# beverage-flow-meters-board.net
KiCad netlist of a schematic drawn in EAGLE
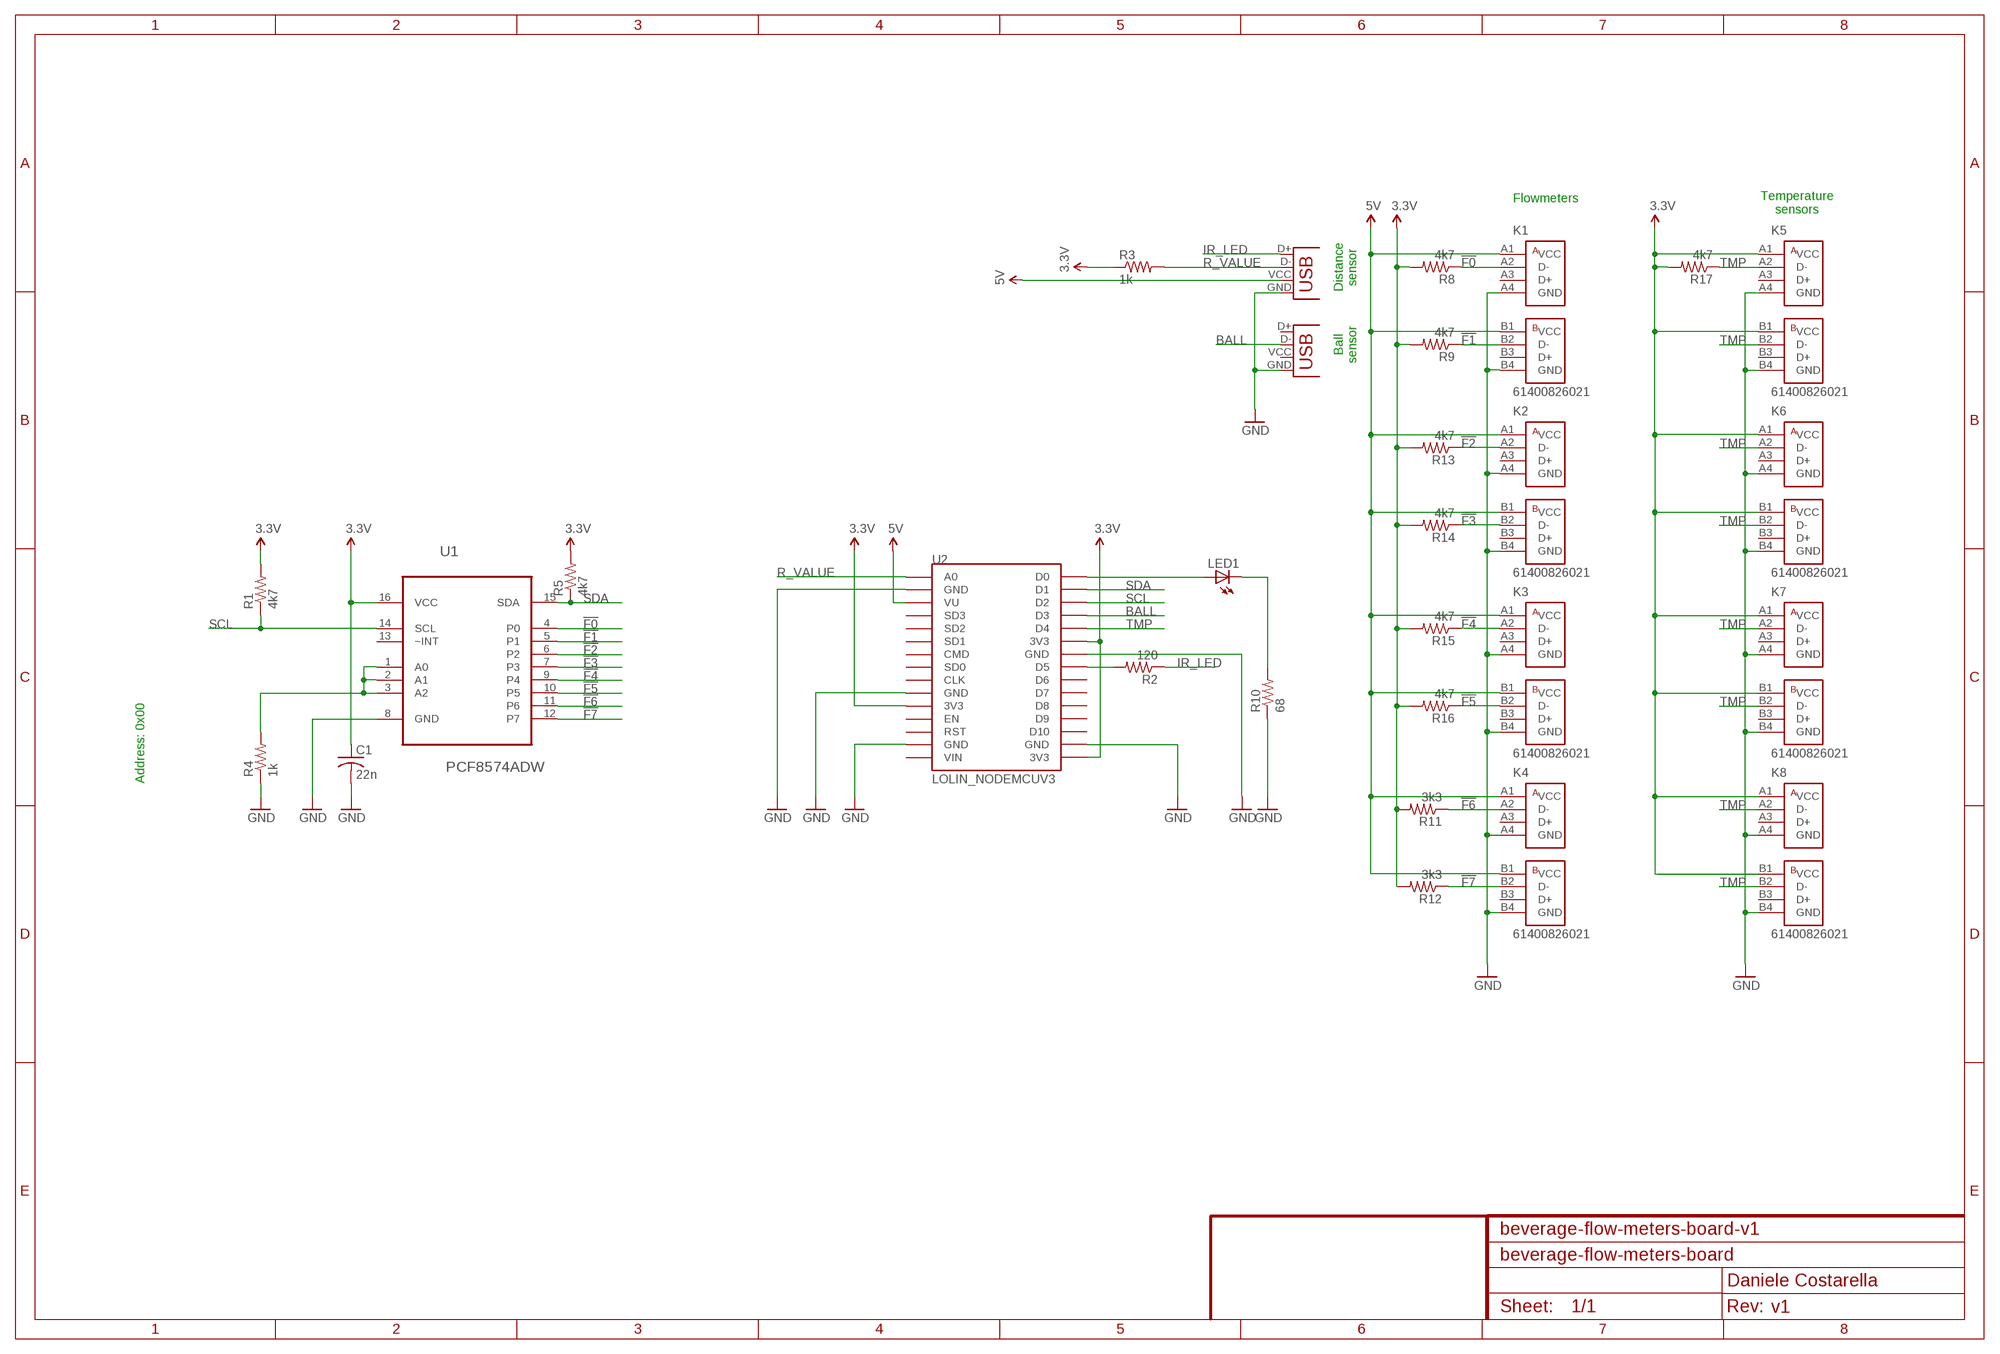
[diagram p0: schematic, sheet 1]

(export (version "E")
  (design (tool "Eeschema 10.0.6"))
  (components
    (comp (ref "C1")
      (value "22n")
      (footprint "eagle-import:C1206")
      (libsource (lib "eagle-import") (part "C-USC1206"))
    )
    (comp (ref "JP1")
      (value "USB-A-H")
      (footprint "eagle-import:USB-A-VERT")
      (libsource (lib "eagle-import") (part "USB-A-H"))
    )
    (comp (ref "JP2")
      (value "USB-A-H")
      (footprint "eagle-import:USB-A-VERT")
      (libsource (lib "eagle-import") (part "USB-A-H"))
    )
    (comp (ref "K1")
      (value "61400826021")
      (footprint "eagle-import:61400826021")
      (libsource (lib "eagle-import") (part "61400826021"))
    )
    (comp (ref "K2")
      (value "61400826021")
      (footprint "eagle-import:61400826021")
      (libsource (lib "eagle-import") (part "61400826021"))
    )
    (comp (ref "K3")
      (value "61400826021")
      (footprint "eagle-import:61400826021")
      (libsource (lib "eagle-import") (part "61400826021"))
    )
    (comp (ref "K4")
      (value "61400826021")
      (footprint "eagle-import:61400826021")
      (libsource (lib "eagle-import") (part "61400826021"))
    )
    (comp (ref "K5")
      (value "61400826021")
      (footprint "eagle-import:61400826021")
      (libsource (lib "eagle-import") (part "61400826021"))
    )
    (comp (ref "K6")
      (value "61400826021")
      (footprint "eagle-import:61400826021")
      (libsource (lib "eagle-import") (part "61400826021"))
    )
    (comp (ref "K7")
      (value "61400826021")
      (footprint "eagle-import:61400826021")
      (libsource (lib "eagle-import") (part "61400826021"))
    )
    (comp (ref "K8")
      (value "61400826021")
      (footprint "eagle-import:61400826021")
      (libsource (lib "eagle-import") (part "61400826021"))
    )
    (comp (ref "LED1")
      (value "LEDCHIP-LED0603")
      (footprint "eagle-import:CHIP-LED0603")
      (libsource (lib "eagle-import") (part "LEDCHIP-LED0603"))
    )
    (comp (ref "R1")
      (value "4k7")
      (footprint "eagle-import:R0603")
      (libsource (lib "eagle-import") (part "R-US_R0603"))
    )
    (comp (ref "R2")
      (value "120")
      (footprint "eagle-import:R0603")
      (libsource (lib "eagle-import") (part "R-US_R0603"))
    )
    (comp (ref "R3")
      (value "1k")
      (footprint "eagle-import:R0603")
      (libsource (lib "eagle-import") (part "R-US_R0603"))
    )
    (comp (ref "R4")
      (value "1k")
      (footprint "eagle-import:R0603")
      (libsource (lib "eagle-import") (part "R-US_R0603"))
    )
    (comp (ref "R5")
      (value "4k7")
      (footprint "eagle-import:R0603")
      (libsource (lib "eagle-import") (part "R-US_R0603"))
    )
    (comp (ref "R8")
      (value "4k7")
      (footprint "eagle-import:R0603")
      (libsource (lib "eagle-import") (part "R-US_R0603"))
    )
    (comp (ref "R9")
      (value "4k7")
      (footprint "eagle-import:R0603")
      (libsource (lib "eagle-import") (part "R-US_R0603"))
    )
    (comp (ref "R10")
      (value "68")
      (footprint "eagle-import:R0603")
      (libsource (lib "eagle-import") (part "R-US_R0603"))
    )
    (comp (ref "R11")
      (value "3k3")
      (footprint "eagle-import:R0603")
      (libsource (lib "eagle-import") (part "R-US_R0603"))
    )
    (comp (ref "R12")
      (value "3k3")
      (footprint "eagle-import:R0603")
      (libsource (lib "eagle-import") (part "R-US_R0603"))
    )
    (comp (ref "R13")
      (value "4k7")
      (footprint "eagle-import:R0603")
      (libsource (lib "eagle-import") (part "R-US_R0603"))
    )
    (comp (ref "R14")
      (value "4k7")
      (footprint "eagle-import:R0603")
      (libsource (lib "eagle-import") (part "R-US_R0603"))
    )
    (comp (ref "R15")
      (value "4k7")
      (footprint "eagle-import:R0603")
      (libsource (lib "eagle-import") (part "R-US_R0603"))
    )
    (comp (ref "R16")
      (value "4k7")
      (footprint "eagle-import:R0603")
      (libsource (lib "eagle-import") (part "R-US_R0603"))
    )
    (comp (ref "R17")
      (value "4k7")
      (footprint "eagle-import:R0603")
      (libsource (lib "eagle-import") (part "R-US_R0603"))
    )
    (comp (ref "U1")
      (value "PCF8574ADW")
      (footprint "eagle-import:SOIC127P1030X265-16N")
      (libsource (lib "eagle-import") (part "PCF8574ADW"))
    )
    (comp (ref "U2")
      (value "LOLIN_NODEMCUV3")
      (footprint "eagle-import:ESP12E_DEVKIT_CHINA")
      (libsource (lib "eagle-import") (part "LOLIN_NODEMCUV3"))
    )
  )
  (nets
    (net (code "1") (name "/BALL") (class "Default")
      (node (ref "JP2") (pin "D-") (pinfunction "D-_D-") (pintype "bidirectional"))
      (node (ref "U2") (pin "D3") (pinfunction "D3_D3") (pintype "bidirectional"))
    )
    (net (code "2") (name "/IR_LED") (class "Default")
      (node (ref "JP1") (pin "D+") (pinfunction "D+_D+") (pintype "bidirectional"))
      (node (ref "R2") (pin "1") (pinfunction "1_1") (pintype "passive"))
    )
    (net (code "3") (name "/R_VALUE") (class "Default")
      (node (ref "JP1") (pin "D-") (pinfunction "D-_D-") (pintype "bidirectional"))
      (node (ref "R3") (pin "2") (pinfunction "2_2") (pintype "passive"))
      (node (ref "U2") (pin "A0") (pinfunction "A0_A0") (pintype "bidirectional"))
    )
    (net (code "4") (name "/SCL") (class "Default")
      (node (ref "R1") (pin "1") (pinfunction "1_1") (pintype "passive"))
      (node (ref "U1") (pin "14") (pinfunction "SCL_14") (pintype "input"))
      (node (ref "U2") (pin "D2") (pinfunction "D2_D2") (pintype "bidirectional"))
    )
    (net (code "5") (name "/SDA") (class "Default")
      (node (ref "R5") (pin "1") (pinfunction "1_1") (pintype "passive"))
      (node (ref "U1") (pin "15") (pinfunction "SDA_15") (pintype "bidirectional"))
      (node (ref "U2") (pin "D1") (pinfunction "D1_D1") (pintype "bidirectional"))
    )
    (net (code "6") (name "/TMP") (class "Default")
      (node (ref "K5") (pin "A2") (pinfunction "D-_A2") (pintype "bidirectional"))
      (node (ref "K5") (pin "B2") (pinfunction "D-_B2") (pintype "bidirectional"))
      (node (ref "K6") (pin "A2") (pinfunction "D-_A2") (pintype "bidirectional"))
      (node (ref "K6") (pin "B2") (pinfunction "D-_B2") (pintype "bidirectional"))
      (node (ref "K7") (pin "A2") (pinfunction "D-_A2") (pintype "bidirectional"))
      (node (ref "K7") (pin "B2") (pinfunction "D-_B2") (pintype "bidirectional"))
      (node (ref "K8") (pin "A2") (pinfunction "D-_A2") (pintype "bidirectional"))
      (node (ref "K8") (pin "B2") (pinfunction "D-_B2") (pintype "bidirectional"))
      (node (ref "R17") (pin "1") (pinfunction "1_1") (pintype "passive"))
      (node (ref "U2") (pin "D4") (pinfunction "D4_D4") (pintype "bidirectional"))
    )
    (net (code "7") (name "/~{F0}") (class "Default")
      (node (ref "K1") (pin "A2") (pinfunction "D-_A2") (pintype "bidirectional"))
      (node (ref "R8") (pin "1") (pinfunction "1_1") (pintype "passive"))
      (node (ref "U1") (pin "4") (pinfunction "P0_4") (pintype "bidirectional"))
    )
    (net (code "8") (name "/~{F1}") (class "Default")
      (node (ref "K1") (pin "B2") (pinfunction "D-_B2") (pintype "bidirectional"))
      (node (ref "R9") (pin "1") (pinfunction "1_1") (pintype "passive"))
      (node (ref "U1") (pin "5") (pinfunction "P1_5") (pintype "bidirectional"))
    )
    (net (code "9") (name "/~{F2}") (class "Default")
      (node (ref "K2") (pin "A2") (pinfunction "D-_A2") (pintype "bidirectional"))
      (node (ref "R13") (pin "1") (pinfunction "1_1") (pintype "passive"))
      (node (ref "U1") (pin "6") (pinfunction "P2_6") (pintype "bidirectional"))
    )
    (net (code "10") (name "/~{F3}") (class "Default")
      (node (ref "K2") (pin "B2") (pinfunction "D-_B2") (pintype "bidirectional"))
      (node (ref "R14") (pin "1") (pinfunction "1_1") (pintype "passive"))
      (node (ref "U1") (pin "7") (pinfunction "P3_7") (pintype "bidirectional"))
    )
    (net (code "11") (name "/~{F4}") (class "Default")
      (node (ref "K3") (pin "A2") (pinfunction "D-_A2") (pintype "bidirectional"))
      (node (ref "R15") (pin "1") (pinfunction "1_1") (pintype "passive"))
      (node (ref "U1") (pin "9") (pinfunction "P4_9") (pintype "bidirectional"))
    )
    (net (code "12") (name "/~{F5}") (class "Default")
      (node (ref "K3") (pin "B2") (pinfunction "D-_B2") (pintype "bidirectional"))
      (node (ref "R16") (pin "1") (pinfunction "1_1") (pintype "passive"))
      (node (ref "U1") (pin "10") (pinfunction "P5_10") (pintype "bidirectional"))
    )
    (net (code "13") (name "/~{F6}") (class "Default")
      (node (ref "K4") (pin "A2") (pinfunction "D-_A2") (pintype "bidirectional"))
      (node (ref "R11") (pin "1") (pinfunction "1_1") (pintype "passive"))
      (node (ref "U1") (pin "11") (pinfunction "P6_11") (pintype "bidirectional"))
    )
    (net (code "14") (name "/~{F7}") (class "Default")
      (node (ref "K4") (pin "B2") (pinfunction "D-_B2") (pintype "bidirectional"))
      (node (ref "R12") (pin "1") (pinfunction "1_1") (pintype "passive"))
      (node (ref "U1") (pin "12") (pinfunction "P7_12") (pintype "bidirectional"))
    )
    (net (code "15") (name "3.3V") (class "Default")
      (node (ref "C1") (pin "1") (pinfunction "1_1") (pintype "passive"))
      (node (ref "K5") (pin "A1") (pinfunction "VCC_A1") (pintype "bidirectional"))
      (node (ref "K5") (pin "B1") (pinfunction "VCC_B1") (pintype "bidirectional"))
      (node (ref "K6") (pin "A1") (pinfunction "VCC_A1") (pintype "bidirectional"))
      (node (ref "K6") (pin "B1") (pinfunction "VCC_B1") (pintype "bidirectional"))
      (node (ref "K7") (pin "A1") (pinfunction "VCC_A1") (pintype "bidirectional"))
      (node (ref "K7") (pin "B1") (pinfunction "VCC_B1") (pintype "bidirectional"))
      (node (ref "K8") (pin "A1") (pinfunction "VCC_A1") (pintype "bidirectional"))
      (node (ref "K8") (pin "B1") (pinfunction "VCC_B1") (pintype "bidirectional"))
      (node (ref "R1") (pin "2") (pinfunction "2_2") (pintype "passive"))
      (node (ref "R11") (pin "2") (pinfunction "2_2") (pintype "passive"))
      (node (ref "R12") (pin "2") (pinfunction "2_2") (pintype "passive"))
      (node (ref "R13") (pin "2") (pinfunction "2_2") (pintype "passive"))
      (node (ref "R14") (pin "2") (pinfunction "2_2") (pintype "passive"))
      (node (ref "R15") (pin "2") (pinfunction "2_2") (pintype "passive"))
      (node (ref "R16") (pin "2") (pinfunction "2_2") (pintype "passive"))
      (node (ref "R17") (pin "2") (pinfunction "2_2") (pintype "passive"))
      (node (ref "R3") (pin "1") (pinfunction "1_1") (pintype "passive"))
      (node (ref "R5") (pin "2") (pinfunction "2_2") (pintype "passive"))
      (node (ref "R8") (pin "2") (pinfunction "2_2") (pintype "passive"))
      (node (ref "R9") (pin "2") (pinfunction "2_2") (pintype "passive"))
      (node (ref "U1") (pin "16") (pinfunction "VCC_16") (pintype "power_in"))
      (node (ref "U2") (pin "3V3@0") (pinfunction "3V3_3V3@0") (pintype "bidirectional"))
      (node (ref "U2") (pin "3V3@1") (pinfunction "3V3_3V3@1") (pintype "bidirectional"))
      (node (ref "U2") (pin "3V3@2") (pinfunction "3V3_3V3@2") (pintype "bidirectional"))
    )
    (net (code "16") (name "5V") (class "Default")
      (node (ref "JP1") (pin "VCC") (pinfunction "VBUS_VCC") (pintype "bidirectional"))
      (node (ref "K1") (pin "A1") (pinfunction "VCC_A1") (pintype "bidirectional"))
      (node (ref "K1") (pin "B1") (pinfunction "VCC_B1") (pintype "bidirectional"))
      (node (ref "K2") (pin "A1") (pinfunction "VCC_A1") (pintype "bidirectional"))
      (node (ref "K2") (pin "B1") (pinfunction "VCC_B1") (pintype "bidirectional"))
      (node (ref "K3") (pin "A1") (pinfunction "VCC_A1") (pintype "bidirectional"))
      (node (ref "K3") (pin "B1") (pinfunction "VCC_B1") (pintype "bidirectional"))
      (node (ref "K4") (pin "A1") (pinfunction "VCC_A1") (pintype "bidirectional"))
      (node (ref "K4") (pin "B1") (pinfunction "VCC_B1") (pintype "bidirectional"))
      (node (ref "U2") (pin "VU") (pinfunction "VU_VU") (pintype "bidirectional"))
    )
    (net (code "17") (name "GND") (class "Default")
      (node (ref "C1") (pin "2") (pinfunction "2_2") (pintype "passive"))
      (node (ref "JP1") (pin "GND") (pinfunction "GND_GND") (pintype "bidirectional"))
      (node (ref "JP2") (pin "GND") (pinfunction "GND_GND") (pintype "bidirectional"))
      (node (ref "K1") (pin "A4") (pinfunction "GND_A4") (pintype "bidirectional"))
      (node (ref "K1") (pin "B4") (pinfunction "GND_B4") (pintype "bidirectional"))
      (node (ref "K2") (pin "A4") (pinfunction "GND_A4") (pintype "bidirectional"))
      (node (ref "K2") (pin "B4") (pinfunction "GND_B4") (pintype "bidirectional"))
      (node (ref "K3") (pin "A4") (pinfunction "GND_A4") (pintype "bidirectional"))
      (node (ref "K3") (pin "B4") (pinfunction "GND_B4") (pintype "bidirectional"))
      (node (ref "K4") (pin "A4") (pinfunction "GND_A4") (pintype "bidirectional"))
      (node (ref "K4") (pin "B4") (pinfunction "GND_B4") (pintype "bidirectional"))
      (node (ref "K5") (pin "A4") (pinfunction "GND_A4") (pintype "bidirectional"))
      (node (ref "K5") (pin "B4") (pinfunction "GND_B4") (pintype "bidirectional"))
      (node (ref "K6") (pin "A4") (pinfunction "GND_A4") (pintype "bidirectional"))
      (node (ref "K6") (pin "B4") (pinfunction "GND_B4") (pintype "bidirectional"))
      (node (ref "K7") (pin "A4") (pinfunction "GND_A4") (pintype "bidirectional"))
      (node (ref "K7") (pin "B4") (pinfunction "GND_B4") (pintype "bidirectional"))
      (node (ref "K8") (pin "A4") (pinfunction "GND_A4") (pintype "bidirectional"))
      (node (ref "K8") (pin "B4") (pinfunction "GND_B4") (pintype "bidirectional"))
      (node (ref "R10") (pin "1") (pinfunction "1_1") (pintype "passive"))
      (node (ref "R4") (pin "1") (pinfunction "1_1") (pintype "passive"))
      (node (ref "U1") (pin "8") (pinfunction "GND_8") (pintype "passive"))
      (node (ref "U2") (pin "GND@0") (pinfunction "GND_GND@0") (pintype "bidirectional"))
      (node (ref "U2") (pin "GND@1") (pinfunction "GND_GND@1") (pintype "bidirectional"))
      (node (ref "U2") (pin "GND@2") (pinfunction "GND_GND@2") (pintype "bidirectional"))
      (node (ref "U2") (pin "GND@3") (pinfunction "GND_GND@3") (pintype "bidirectional"))
      (node (ref "U2") (pin "GND@4") (pinfunction "GND_GND@4") (pintype "bidirectional"))
    )
    (net (code "18") (name "Net-(LED1-PadA)") (class "Default")
      (node (ref "LED1") (pin "A") (pinfunction "A_A") (pintype "passive"))
      (node (ref "U2") (pin "D0") (pinfunction "D0_D0") (pintype "bidirectional"))
    )
    (net (code "19") (name "Net-(LED1-PadC)") (class "Default")
      (node (ref "LED1") (pin "C") (pinfunction "C_C") (pintype "passive"))
      (node (ref "R10") (pin "2") (pinfunction "2_2") (pintype "passive"))
    )
    (net (code "20") (name "Net-(R2-Pad2)") (class "Default")
      (node (ref "R2") (pin "2") (pinfunction "2_2") (pintype "passive"))
      (node (ref "U2") (pin "D5") (pinfunction "D5_D5") (pintype "bidirectional"))
    )
    (net (code "21") (name "Net-(U1-A0)") (class "Default")
      (node (ref "R4") (pin "2") (pinfunction "2_2") (pintype "passive"))
      (node (ref "U1") (pin "1") (pinfunction "A0_1") (pintype "input"))
      (node (ref "U1") (pin "2") (pinfunction "A1_2") (pintype "input"))
      (node (ref "U1") (pin "3") (pinfunction "A2_3") (pintype "input"))
    )
    (net (code "22") (name "unconnected-(JP2-PadD+)") (class "Default")
      (node (ref "JP2") (pin "D+") (pinfunction "D+_D+") (pintype "bidirectional"))
    )
    (net (code "23") (name "unconnected-(JP2-VBUS-PadVCC)") (class "Default")
      (node (ref "JP2") (pin "VCC") (pinfunction "VBUS_VCC") (pintype "bidirectional"))
    )
    (net (code "24") (name "unconnected-(K1-D+-PadA3)") (class "Default")
      (node (ref "K1") (pin "A3") (pinfunction "D+_A3") (pintype "bidirectional"))
    )
    (net (code "25") (name "unconnected-(K1-D+-PadB3)") (class "Default")
      (node (ref "K1") (pin "B3") (pinfunction "D+_B3") (pintype "bidirectional"))
    )
    (net (code "26") (name "unconnected-(K2-D+-PadA3)") (class "Default")
      (node (ref "K2") (pin "A3") (pinfunction "D+_A3") (pintype "bidirectional"))
    )
    (net (code "27") (name "unconnected-(K2-D+-PadB3)") (class "Default")
      (node (ref "K2") (pin "B3") (pinfunction "D+_B3") (pintype "bidirectional"))
    )
    (net (code "28") (name "unconnected-(K3-D+-PadA3)") (class "Default")
      (node (ref "K3") (pin "A3") (pinfunction "D+_A3") (pintype "bidirectional"))
    )
    (net (code "29") (name "unconnected-(K3-D+-PadB3)") (class "Default")
      (node (ref "K3") (pin "B3") (pinfunction "D+_B3") (pintype "bidirectional"))
    )
    (net (code "30") (name "unconnected-(K4-D+-PadA3)") (class "Default")
      (node (ref "K4") (pin "A3") (pinfunction "D+_A3") (pintype "bidirectional"))
    )
    (net (code "31") (name "unconnected-(K4-D+-PadB3)") (class "Default")
      (node (ref "K4") (pin "B3") (pinfunction "D+_B3") (pintype "bidirectional"))
    )
    (net (code "32") (name "unconnected-(K5-D+-PadA3)") (class "Default")
      (node (ref "K5") (pin "A3") (pinfunction "D+_A3") (pintype "bidirectional"))
    )
    (net (code "33") (name "unconnected-(K5-D+-PadB3)") (class "Default")
      (node (ref "K5") (pin "B3") (pinfunction "D+_B3") (pintype "bidirectional"))
    )
    (net (code "34") (name "unconnected-(K6-D+-PadA3)") (class "Default")
      (node (ref "K6") (pin "A3") (pinfunction "D+_A3") (pintype "bidirectional"))
    )
    (net (code "35") (name "unconnected-(K6-D+-PadB3)") (class "Default")
      (node (ref "K6") (pin "B3") (pinfunction "D+_B3") (pintype "bidirectional"))
    )
    (net (code "36") (name "unconnected-(K7-D+-PadA3)") (class "Default")
      (node (ref "K7") (pin "A3") (pinfunction "D+_A3") (pintype "bidirectional"))
    )
    (net (code "37") (name "unconnected-(K7-D+-PadB3)") (class "Default")
      (node (ref "K7") (pin "B3") (pinfunction "D+_B3") (pintype "bidirectional"))
    )
    (net (code "38") (name "unconnected-(K8-D+-PadA3)") (class "Default")
      (node (ref "K8") (pin "A3") (pinfunction "D+_A3") (pintype "bidirectional"))
    )
    (net (code "39") (name "unconnected-(K8-D+-PadB3)") (class "Default")
      (node (ref "K8") (pin "B3") (pinfunction "D+_B3") (pintype "bidirectional"))
    )
    (net (code "40") (name "unconnected-(U1-~{INT}-Pad13)") (class "Default")
      (node (ref "U1") (pin "13") (pinfunction "~{INT}_13") (pintype "input"))
    )
    (net (code "41") (name "unconnected-(U2-D9-PadRX)") (class "Default")
      (node (ref "U2") (pin "RX") (pinfunction "D9_RX") (pintype "bidirectional"))
    )
    (net (code "42") (name "unconnected-(U2-D10-PadTX)") (class "Default")
      (node (ref "U2") (pin "TX") (pinfunction "D10_TX") (pintype "bidirectional"))
    )
    (net (code "43") (name "unconnected-(U2-PadCLK)") (class "Default")
      (node (ref "U2") (pin "CLK") (pinfunction "CLK_CLK") (pintype "bidirectional"))
    )
    (net (code "44") (name "unconnected-(U2-PadCMD)") (class "Default")
      (node (ref "U2") (pin "CMD") (pinfunction "CMD_CMD") (pintype "bidirectional"))
    )
    (net (code "45") (name "unconnected-(U2-PadD6)") (class "Default")
      (node (ref "U2") (pin "D6") (pinfunction "D6_D6") (pintype "bidirectional"))
    )
    (net (code "46") (name "unconnected-(U2-PadD7)") (class "Default")
      (node (ref "U2") (pin "D7") (pinfunction "D7_D7") (pintype "bidirectional"))
    )
    (net (code "47") (name "unconnected-(U2-PadD8)") (class "Default")
      (node (ref "U2") (pin "D8") (pinfunction "D8_D8") (pintype "bidirectional"))
    )
    (net (code "48") (name "unconnected-(U2-PadEN)") (class "Default")
      (node (ref "U2") (pin "EN") (pinfunction "EN_EN") (pintype "bidirectional"))
    )
    (net (code "49") (name "unconnected-(U2-PadRST)") (class "Default")
      (node (ref "U2") (pin "RST") (pinfunction "RST_RST") (pintype "bidirectional"))
    )
    (net (code "50") (name "unconnected-(U2-PadSD0)") (class "Default")
      (node (ref "U2") (pin "SD0") (pinfunction "SD0_SD0") (pintype "bidirectional"))
    )
    (net (code "51") (name "unconnected-(U2-PadSD1)") (class "Default")
      (node (ref "U2") (pin "SD1") (pinfunction "SD1_SD1") (pintype "bidirectional"))
    )
    (net (code "52") (name "unconnected-(U2-PadSD2)") (class "Default")
      (node (ref "U2") (pin "SD2") (pinfunction "SD2_SD2") (pintype "bidirectional"))
    )
    (net (code "53") (name "unconnected-(U2-PadSD3)") (class "Default")
      (node (ref "U2") (pin "SD3") (pinfunction "SD3_SD3") (pintype "bidirectional"))
    )
    (net (code "54") (name "unconnected-(U2-PadVIN)") (class "Default")
      (node (ref "U2") (pin "VIN") (pinfunction "VIN_VIN") (pintype "bidirectional"))
    )
  )
)
